# nusense-otg_hs_usb.net
KiCad netlist of a schematic drawn in Altium Designer
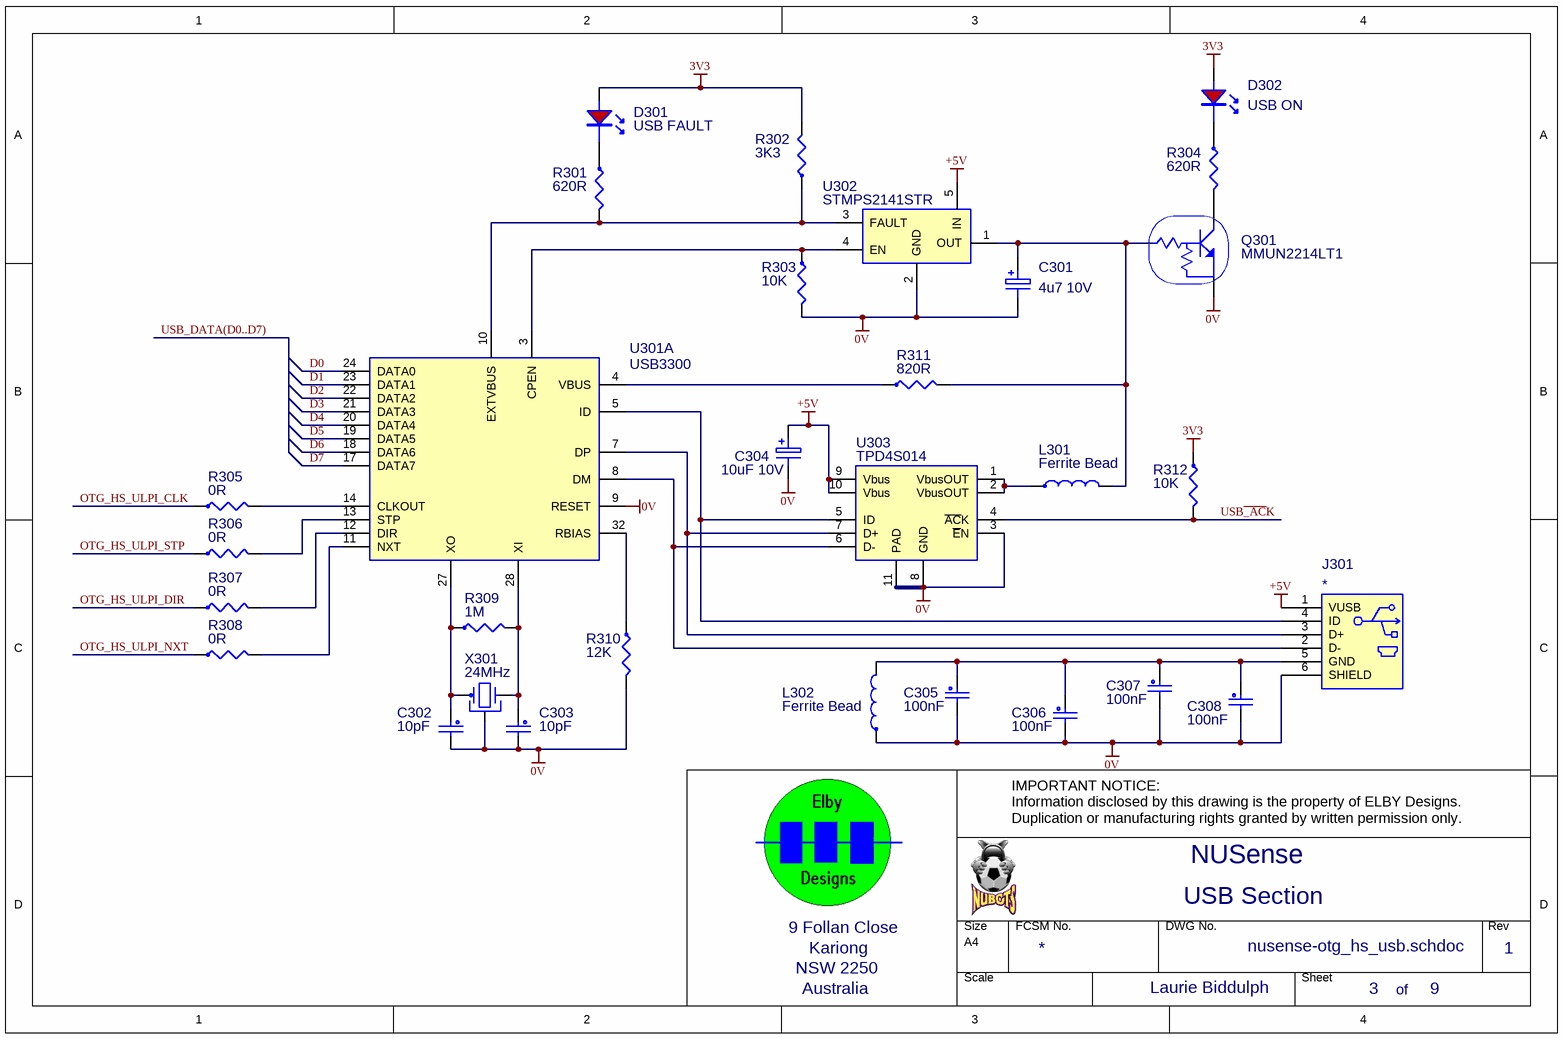
[diagram p0: nusense-otg_hs_usb.schdoc]

(export (version "E")
  (design (tool "Eeschema 10.0.6"))
  (components
    (comp (ref "C301")
      (value "4u7 10V")
      (footprint "RB-D5.0-P2.0")
      (description "20% 50V Aluminium Electrolytic")
      (libsource (lib "capacitor") (part "CE-4U7F50V(LB)"))
    )
    (comp (ref "C302")
      (value "10pF")
      (footprint "RAD-0.2N(LB)")
      (description "NPO Low K, 50VDC Ceramic Disc")
      (libsource (lib "capacitor") (part "CC-10PF(LB)"))
    )
    (comp (ref "C303")
      (value "10pF")
      (footprint "RAD-0.2N(LB)")
      (description "NPO Low K, 50VDC Ceramic Disc")
      (libsource (lib "capacitor") (part "CC-10PF(LB)"))
    )
    (comp (ref "C304")
      (value "10uF 10V")
      (footprint "RB-D6.3-P2.5")
      (description "20% 50V Aluminium Electrolytic")
      (libsource (lib "capacitor") (part "CE-10UF50V(LB)"))
    )
    (comp (ref "C305")
      (value "100nF")
      (footprint "RAD-0.2N(LB)")
      (description "Monolithic Ceramic")
      (libsource (lib "capacitor") (part "CC-100NF(LB)"))
    )
    (comp (ref "C306")
      (value "100nF")
      (footprint "RAD-0.2N(LB)")
      (description "Monolithic Ceramic")
      (libsource (lib "capacitor") (part "CC-100NF(LB)"))
    )
    (comp (ref "C307")
      (value "100nF")
      (footprint "RAD-0.2N(LB)")
      (description "Monolithic Ceramic")
      (libsource (lib "capacitor") (part "CC-100NF(LB)"))
    )
    (comp (ref "C308")
      (value "100nF")
      (footprint "RAD-0.2N(LB)")
      (description "Monolithic Ceramic")
      (libsource (lib "capacitor") (part "CC-100NF(LB)"))
    )
    (comp (ref "D301")
      (value "USB FAULT")
      (footprint "LED-PCB(LB)")
      (description "LED")
      (libsource (lib "semi") (part "LED-RED(LB)"))
    )
    (comp (ref "D302")
      (value "USB ON")
      (footprint "LED-PCB(LB)")
      (description "LED")
      (libsource (lib "semi") (part "LED-RED(LB)"))
    )
    (comp (ref "J301") (value "*") (libsource (lib "NuBots") (part "ZX62D-B-5P8")))
    (comp (ref "L301")
      (value "Ferrite Bead")
      (footprint "AXIAL-0.3IND(LB)")
      (libsource (lib "passive") (part "FERRITE-BEAD(LB)"))
    )
    (comp (ref "L302")
      (value "Ferrite Bead")
      (footprint "AXIAL-0.3IND(LB)")
      (libsource (lib "") (part "FERRITE-BEAD(LB)_1"))
    )
    (comp (ref "Q301")
      (value "MMUN2214LT1")
      (footprint "SOT-23(LB)")
      (description "NPN Digital Transistor")
      (libsource (lib "semi") (part "MMUN2214LT1(SMD)"))
    )
    (comp (ref "R301")
      (value "620R")
      (footprint "AXIAL-0.4(LB)")
      (description "0.5W 1% Metal Film Resistor")
      (libsource (lib "resistor") (part "RM-620R(LB)"))
    )
    (comp (ref "R302")
      (value "3K3")
      (footprint "AXIAL-0.4(LB)")
      (description "0.5W 1% Metal Film Resistor")
      (libsource (lib "resistor") (part "RM-3K3(LB)"))
    )
    (comp (ref "R303")
      (value "10K")
      (footprint "AXIAL-0.4(LB)")
      (description "0.5W 1% Metal Film Resistor")
      (libsource (lib "resistor") (part "RM-10K(LB)"))
    )
    (comp (ref "R304")
      (value "620R")
      (footprint "AXIAL-0.4(LB)")
      (description "0.5W 1% Metal Film Resistor")
      (libsource (lib "resistor") (part "RM-620R(LB)"))
    )
    (comp (ref "R305")
      (value "0R")
      (footprint "AXIAL-0.4(LB)")
      (description "Resistor - Short Circuit")
      (libsource (lib "resistor") (part "RM-SC(LB)"))
    )
    (comp (ref "R306")
      (value "0R")
      (footprint "AXIAL-0.4(LB)")
      (description "Resistor - Short Circuit")
      (libsource (lib "resistor") (part "RM-SC(LB)"))
    )
    (comp (ref "R307")
      (value "0R")
      (footprint "AXIAL-0.4(LB)")
      (description "Resistor - Short Circuit")
      (libsource (lib "resistor") (part "RM-SC(LB)"))
    )
    (comp (ref "R308")
      (value "0R")
      (footprint "AXIAL-0.4(LB)")
      (description "Resistor - Short Circuit")
      (libsource (lib "resistor") (part "RM-SC(LB)"))
    )
    (comp (ref "R309")
      (value "1M")
      (footprint "AXIAL-0.4(LB)")
      (description "0.5W 1% Metal Film Resistor")
      (libsource (lib "resistor") (part "RM-1M(LB)"))
    )
    (comp (ref "R310")
      (value "12K")
      (footprint "AXIAL-0.4(LB)")
      (description "0.5W 1% Metal Film Resistor")
      (libsource (lib "resistor") (part "RM-12K(LB)"))
    )
    (comp (ref "R311")
      (value "820R")
      (footprint "AXIAL-0.4(LB)")
      (description "0.5W 1% Metal Film Resistor")
      (libsource (lib "resistor") (part "RM-820R(LB)"))
    )
    (comp (ref "R312")
      (value "10K")
      (footprint "AXIAL-0.4(LB)")
      (description "0.5W 1% Metal Film Resistor")
      (libsource (lib "resistor") (part "RM-10K(LB)"))
    )
    (comp (ref "U301")
      (value "USB3300")
      (footprint "QFN-32_L")
      (description "USB Host Controller")
      (libsource (lib "NuBots") (part "USB3300"))
    )
    (comp (ref "U302")
      (value "STMPS2141STR")
      (footprint "SOT-23-5(LB)")
      (description "Power Switch")
      (libsource (lib "NuBots") (part "STMPS2141"))
    )
    (comp (ref "U303")
      (value "TPD4S014")
      (description "USB Charger Port Protector")
      (libsource (lib "NuBots") (part "TPD4S014"))
    )
    (comp (ref "X301")
      (value "24MHz")
      (footprint "CRYSTAL-3(LB)")
      (description "24MHz Parallel-cut Crystal - HC49")
      (libsource (lib "passive") (part "XTAL-24MHZ(LB)"))
    )
  )
  (nets
    (net (code "2") (name "+5V") (class "Default")
      (node (ref "C304") (pin "1") (pintype "passive"))
      (node (ref "J301") (pin "1") (pinfunction "VUSB_1") (pintype "passive"))
      (node (ref "U302") (pin "5") (pinfunction "IN_5") (pintype "power_in"))
      (node (ref "U303") (pin "10") (pinfunction "Vbus_10") (pintype "power_in"))
      (node (ref "U303") (pin "9") (pinfunction "Vbus_9") (pintype "power_in"))
    )
    (net (code "3") (name "/D0") (class "Default")
      (node (ref "U301") (pin "24") (pinfunction "DATA0_24") (pintype "passive"))
    )
    (net (code "4") (name "/D1") (class "Default")
      (node (ref "U301") (pin "23") (pinfunction "DATA1_23") (pintype "passive"))
    )
    (net (code "5") (name "/D2") (class "Default")
      (node (ref "U301") (pin "22") (pinfunction "DATA2_22") (pintype "passive"))
    )
    (net (code "6") (name "/D3") (class "Default")
      (node (ref "U301") (pin "21") (pinfunction "DATA3_21") (pintype "passive"))
    )
    (net (code "7") (name "/D4") (class "Default")
      (node (ref "U301") (pin "20") (pinfunction "DATA4_20") (pintype "passive"))
    )
    (net (code "8") (name "/D5") (class "Default")
      (node (ref "U301") (pin "19") (pinfunction "DATA5_19") (pintype "passive"))
    )
    (net (code "9") (name "/D6") (class "Default")
      (node (ref "U301") (pin "18") (pinfunction "DATA6_18") (pintype "passive"))
    )
    (net (code "10") (name "/D7") (class "Default")
      (node (ref "U301") (pin "17") (pinfunction "DATA7_17") (pintype "passive"))
    )
    (net (code "11") (name "/OTG_HS_ULPI_CLK") (class "Default")
      (node (ref "R305") (pin "1") (pinfunction "1_1") (pintype "passive"))
    )
    (net (code "12") (name "/OTG_HS_ULPI_DIR") (class "Default")
      (node (ref "R307") (pin "1") (pinfunction "1_1") (pintype "passive"))
    )
    (net (code "13") (name "/OTG_HS_ULPI_NXT") (class "Default")
      (node (ref "R308") (pin "1") (pinfunction "1_1") (pintype "passive"))
    )
    (net (code "14") (name "/OTG_HS_ULPI_STP") (class "Default")
      (node (ref "R306") (pin "1") (pinfunction "1_1") (pintype "passive"))
    )
    (net (code "15") (name "/USB~{_AC}K") (class "Default")
      (node (ref "R312") (pin "2") (pinfunction "2_2") (pintype "passive"))
      (node (ref "U303") (pin "4") (pinfunction "~{AC}K_4") (pintype "passive"))
    )
    (net (code "17") (name "0V") (class "Default")
      (node (ref "C301") (pin "2") (pintype "passive"))
      (node (ref "C302") (pin "2") (pintype "passive"))
      (node (ref "C303") (pin "2") (pintype "passive"))
      (node (ref "C304") (pin "2") (pintype "passive"))
      (node (ref "C305") (pin "2") (pintype "passive"))
      (node (ref "C306") (pin "2") (pintype "passive"))
      (node (ref "C307") (pin "2") (pintype "passive"))
      (node (ref "C308") (pin "2") (pintype "passive"))
      (node (ref "J301") (pin "6") (pinfunction "SHIELD_6") (pintype "passive"))
      (node (ref "L302") (pin "1") (pinfunction "1_1") (pintype "passive"))
      (node (ref "Q301") (pin "2") (pinfunction "E_2") (pintype "passive"))
      (node (ref "R303") (pin "2") (pinfunction "2_2") (pintype "passive"))
      (node (ref "R310") (pin "2") (pinfunction "2_2") (pintype "passive"))
      (node (ref "U301") (pin "9") (pinfunction "RESET_9") (pintype "passive"))
      (node (ref "U302") (pin "2") (pinfunction "GND_2") (pintype "power_in"))
      (node (ref "U303") (pin "11") (pinfunction "PAD_11") (pintype "power_in"))
      (node (ref "U303") (pin "3") (pinfunction "~{E}N_3") (pintype "passive"))
      (node (ref "U303") (pin "8") (pinfunction "GND_8") (pintype "power_in"))
      (node (ref "X301") (pin "3") (pinfunction "3_3") (pintype "power_in"))
    )
    (net (code "18") (name "3V3") (class "Default")
      (node (ref "D301") (pin "A") (pinfunction "A_A") (pintype "passive"))
      (node (ref "D302") (pin "A") (pinfunction "A_A") (pintype "passive"))
      (node (ref "R302") (pin "2") (pinfunction "2_2") (pintype "passive"))
      (node (ref "R312") (pin "1") (pinfunction "1_1") (pintype "passive"))
    )
    (net (code "19") (name "Net-(D301-PadK)") (class "Default")
      (node (ref "D301") (pin "K") (pinfunction "K_K") (pintype "passive"))
      (node (ref "R301") (pin "1") (pinfunction "1_1") (pintype "passive"))
    )
    (net (code "20") (name "Net-(D302-PadK)") (class "Default")
      (node (ref "D302") (pin "K") (pinfunction "K_K") (pintype "passive"))
      (node (ref "R304") (pin "1") (pinfunction "1_1") (pintype "passive"))
    )
    (net (code "21") (name "Net-(J301-D+)") (class "Default")
      (node (ref "J301") (pin "3") (pinfunction "D+_3") (pintype "passive"))
      (node (ref "U301") (pin "7") (pinfunction "DP_7") (pintype "passive"))
      (node (ref "U303") (pin "7") (pinfunction "D+_7") (pintype "passive"))
    )
    (net (code "22") (name "Net-(J301-D-)") (class "Default")
      (node (ref "J301") (pin "2") (pinfunction "D-_2") (pintype "passive"))
      (node (ref "U301") (pin "8") (pinfunction "DM_8") (pintype "passive"))
      (node (ref "U303") (pin "6") (pinfunction "D-_6") (pintype "passive"))
    )
    (net (code "23") (name "Net-(J301-GND)") (class "Default")
      (node (ref "C305") (pin "1") (pintype "passive"))
      (node (ref "C306") (pin "1") (pintype "passive"))
      (node (ref "C307") (pin "1") (pintype "passive"))
      (node (ref "C308") (pin "1") (pintype "passive"))
      (node (ref "J301") (pin "5") (pinfunction "GND_5") (pintype "passive"))
      (node (ref "L302") (pin "2") (pinfunction "2_2") (pintype "passive"))
    )
    (net (code "24") (name "Net-(J301-ID)") (class "Default")
      (node (ref "J301") (pin "4") (pinfunction "ID_4") (pintype "passive"))
      (node (ref "U301") (pin "5") (pinfunction "ID_5") (pintype "passive"))
      (node (ref "U303") (pin "5") (pinfunction "ID_5") (pintype "passive"))
    )
    (net (code "25") (name "Net-(L301-Pad1)") (class "Default")
      (node (ref "L301") (pin "1") (pinfunction "1_1") (pintype "passive"))
      (node (ref "U303") (pin "1") (pinfunction "VbusOUT_1") (pintype "power_in"))
      (node (ref "U303") (pin "2") (pinfunction "VbusOUT_2") (pintype "power_in"))
    )
    (net (code "26") (name "Net-(Q301-B)") (class "Default")
      (node (ref "C301") (pin "1") (pintype "passive"))
      (node (ref "L301") (pin "2") (pinfunction "2_2") (pintype "passive"))
      (node (ref "Q301") (pin "1") (pinfunction "B_1") (pintype "passive"))
      (node (ref "R311") (pin "2") (pinfunction "2_2") (pintype "passive"))
      (node (ref "U302") (pin "1") (pinfunction "OUT_1") (pintype "passive"))
    )
    (net (code "27") (name "Net-(Q301-C)") (class "Default")
      (node (ref "Q301") (pin "3") (pinfunction "C_3") (pintype "passive"))
      (node (ref "R304") (pin "2") (pinfunction "2_2") (pintype "passive"))
    )
    (net (code "28") (name "Net-(U301A-CLKOUT)") (class "Default")
      (node (ref "R305") (pin "2") (pinfunction "2_2") (pintype "passive"))
      (node (ref "U301") (pin "14") (pinfunction "CLKOUT_14") (pintype "passive"))
    )
    (net (code "29") (name "Net-(U301A-CPEN)") (class "Default")
      (node (ref "R303") (pin "1") (pinfunction "1_1") (pintype "passive"))
      (node (ref "U301") (pin "3") (pinfunction "CPEN_3") (pintype "passive"))
      (node (ref "U302") (pin "4") (pinfunction "EN_4") (pintype "passive"))
    )
    (net (code "30") (name "Net-(U301A-DIR)") (class "Default")
      (node (ref "R307") (pin "2") (pinfunction "2_2") (pintype "passive"))
      (node (ref "U301") (pin "12") (pinfunction "DIR_12") (pintype "passive"))
    )
    (net (code "31") (name "Net-(U301A-EXTVBUS)") (class "Default")
      (node (ref "R301") (pin "2") (pinfunction "2_2") (pintype "passive"))
      (node (ref "R302") (pin "1") (pinfunction "1_1") (pintype "passive"))
      (node (ref "U301") (pin "10") (pinfunction "EXTVBUS_10") (pintype "passive"))
      (node (ref "U302") (pin "3") (pinfunction "FAULT_3") (pintype "passive"))
    )
    (net (code "32") (name "Net-(U301A-NXT)") (class "Default")
      (node (ref "R308") (pin "2") (pinfunction "2_2") (pintype "passive"))
      (node (ref "U301") (pin "11") (pinfunction "NXT_11") (pintype "passive"))
    )
    (net (code "33") (name "Net-(U301A-RBIAS)") (class "Default")
      (node (ref "R310") (pin "1") (pinfunction "1_1") (pintype "passive"))
      (node (ref "U301") (pin "32") (pinfunction "RBIAS_32") (pintype "passive"))
    )
    (net (code "34") (name "Net-(U301A-STP)") (class "Default")
      (node (ref "R306") (pin "2") (pinfunction "2_2") (pintype "passive"))
      (node (ref "U301") (pin "13") (pinfunction "STP_13") (pintype "passive"))
    )
    (net (code "35") (name "Net-(U301A-VBUS)") (class "Default")
      (node (ref "R311") (pin "1") (pinfunction "1_1") (pintype "passive"))
      (node (ref "U301") (pin "4") (pinfunction "VBUS_4") (pintype "passive"))
    )
    (net (code "36") (name "Net-(U301A-XI)") (class "Default")
      (node (ref "C303") (pin "1") (pintype "passive"))
      (node (ref "R309") (pin "2") (pinfunction "2_2") (pintype "passive"))
      (node (ref "U301") (pin "28") (pinfunction "XI_28") (pintype "passive"))
      (node (ref "X301") (pin "2") (pinfunction "2_2") (pintype "passive"))
    )
    (net (code "37") (name "Net-(U301A-XO)") (class "Default")
      (node (ref "C302") (pin "1") (pintype "passive"))
      (node (ref "R309") (pin "1") (pinfunction "1_1") (pintype "passive"))
      (node (ref "U301") (pin "27") (pinfunction "XO_27") (pintype "passive"))
      (node (ref "X301") (pin "1") (pinfunction "1_1") (pintype "passive"))
    )
  )
)
